# Sheet1.net
KiCad netlist of a schematic drawn in Altium Designer
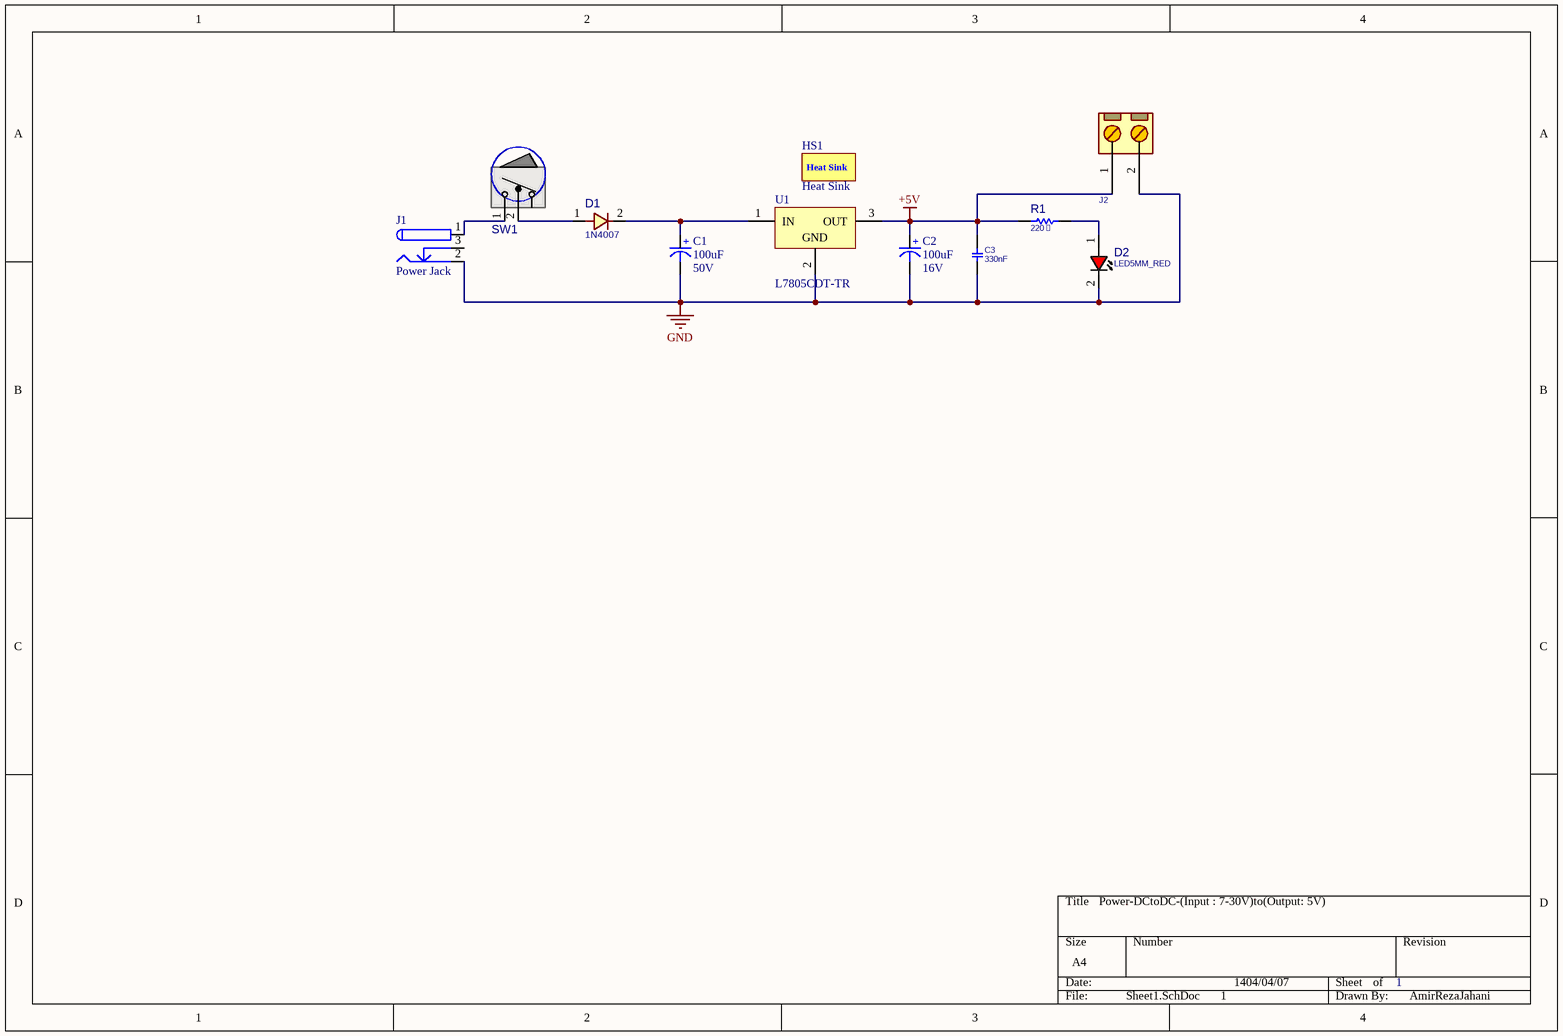
[diagram p0: Sheet1.SchDoc]

(export (version "E")
  (design (tool "Eeschema 10.0.6"))
  (components
    (comp (ref "C1")
      (value "100uF")
      (footprint "cap 01")
      (description "Polar Capacitor")
      (fields (field (name "VOLTAGE") "50V") (field (name "DESIGNER") "Saeid Jorablo"))
      (libsource (lib "My_Library") (part "Cap-Polar"))
    )
    (comp (ref "C2")
      (value "100uF")
      (footprint "cap 01")
      (description "Polar Capacitor")
      (fields (field (name "VOLTAGE") "16V") (field (name "DESIGNER") "Saeid Jorablo"))
      (libsource (lib "My_Library") (part "Cap-Polar"))
    )
    (comp (ref "C3")
      (value "330nF")
      (footprint "C_CERM_D3")
      (description "CAP, THD, CER MULTI LAYER,")
      (fields (field (name "MANF_P#") "MANF_PART#") (field (name "MANF") "MANF"))
      (libsource (lib "passive_thd") (part "CAP_THD_CER"))
    )
    (comp (ref "D1")
      (value "1N4007")
      (footprint "D_AX04_DO41")
      (description "DIODE, GENERAL PURPOSE, 1000V/1A")
      (fields (field (name "MANF") "Diodes"))
      (libsource (lib "diode") (part "DIODE_THD_1N4007"))
    )
    (comp (ref "D2")
      (value "LED5MM_RED")
      (footprint "LED5MM_RED")
      (description "LED, THD, 5MM, RED")
      (fields (field (name "MANF") "MANF") (field (name "MANF_P#") "MANF_PART#"))
      (libsource (lib "led(diode)") (part "LED_THD_5MM_RED"))
    )
    (comp (ref "HS1")
      (value "Heat Sink")
      (footprint "HeatSink PH51")
      (description "PH51 Heatsink")
      (libsource (lib "My_Library") (part "HeatSink PH51"))
    )
    (comp (ref "J1")
      (value "Power Jack")
      (footprint "Power Jack")
      (fields (field (name "DESIGNER") "Saeid Jorablo"))
      (libsource (lib "My_Library") (part "Power Jack"))
    )
    (comp (ref "J2")
      (value "CONN_TB2")
      (footprint "MSTB_2")
      (description "CONN, PHOENIX MSTB, 5-G, 5.08mm pitch")
      (libsource (lib "conn_terminalB") (part "CONN_MSTB_2"))
    )
    (comp (ref "R1")
      (value "220ꭥ")
      (footprint "R025W_AX04")
      (description "RESISTOR, THD")
      (fields (field (name "MANF_P#") "RK73H1ETTP4701F") (field (name "MANF") "KOA SPEER"))
      (libsource (lib "passive_thd") (part "RES_THD"))
    )
    (comp (ref "SW1")
      (value "ToggleSwitch")
      (footprint "SWRCK_SPST_S_15X10")
      (description "SWITCH, Rocker, SPST, THD, 15x10.5mm")
      (libsource (lib "switch_rocker") (part "SWROK_SPST_R_15X10"))
    )
    (comp (ref "U1")
      (value "L7805CDT-TR")
      (footprint "L7805 Right")
      (libsource (lib "L7805CDT-TR") (part "L7805CDT-TR"))
    )
  )
  (nets
    (net (code "1") (name "+5V") (class "Default")
      (node (ref "C2") (pin "1") (pinfunction "+_1") (pintype "passive"))
      (node (ref "C3") (pin "2") (pinfunction "2_2") (pintype "passive"))
      (node (ref "J2") (pin "1") (pinfunction "1_1") (pintype "passive"))
      (node (ref "R1") (pin "2") (pinfunction "2_2") (pintype "passive"))
      (node (ref "U1") (pin "3") (pinfunction "OUT_3") (pintype "power_in"))
    )
    (net (code "2") (name "GND") (class "Default")
      (node (ref "C1") (pin "2") (pinfunction "-_2") (pintype "passive"))
      (node (ref "C2") (pin "2") (pinfunction "-_2") (pintype "passive"))
      (node (ref "C3") (pin "1") (pinfunction "1_1") (pintype "passive"))
      (node (ref "D2") (pin "2") (pinfunction "CATHODE_2") (pintype "passive"))
      (node (ref "J1") (pin "2") (pinfunction "2_2") (pintype "power_in"))
      (node (ref "J2") (pin "2") (pinfunction "2_2") (pintype "passive"))
      (node (ref "U1") (pin "2") (pinfunction "GND_2") (pintype "power_in"))
    )
    (net (code "3") (name "Net-(C1-+)") (class "Default")
      (node (ref "C1") (pin "1") (pinfunction "+_1") (pintype "passive"))
      (node (ref "D1") (pin "2") (pinfunction "2_2") (pintype "passive"))
      (node (ref "U1") (pin "1") (pinfunction "IN_1") (pintype "power_in"))
    )
    (net (code "4") (name "Net-(D2-ANODE)") (class "Default")
      (node (ref "D2") (pin "1") (pinfunction "ANODE_1") (pintype "passive"))
      (node (ref "R1") (pin "1") (pinfunction "1_1") (pintype "passive"))
    )
    (net (code "5") (name "Net-(SW1-COM)") (class "Default")
      (node (ref "D1") (pin "1") (pinfunction "1_1") (pintype "passive"))
      (node (ref "SW1") (pin "2") (pinfunction "COM_2") (pintype "passive"))
    )
    (net (code "6") (name "Net-(SW1-T1)") (class "Default")
      (node (ref "J1") (pin "1") (pinfunction "1_1") (pintype "power_in"))
      (node (ref "SW1") (pin "1") (pinfunction "T1_1") (pintype "passive"))
    )
    (net (code "7") (name "unconnected-(J1-Pad3)") (class "Default")
      (node (ref "J1") (pin "3") (pinfunction "3_3") (pintype "power_in"))
    )
  )
)
